# Sheet2.net
KiCad netlist of a schematic drawn in Altium Designer
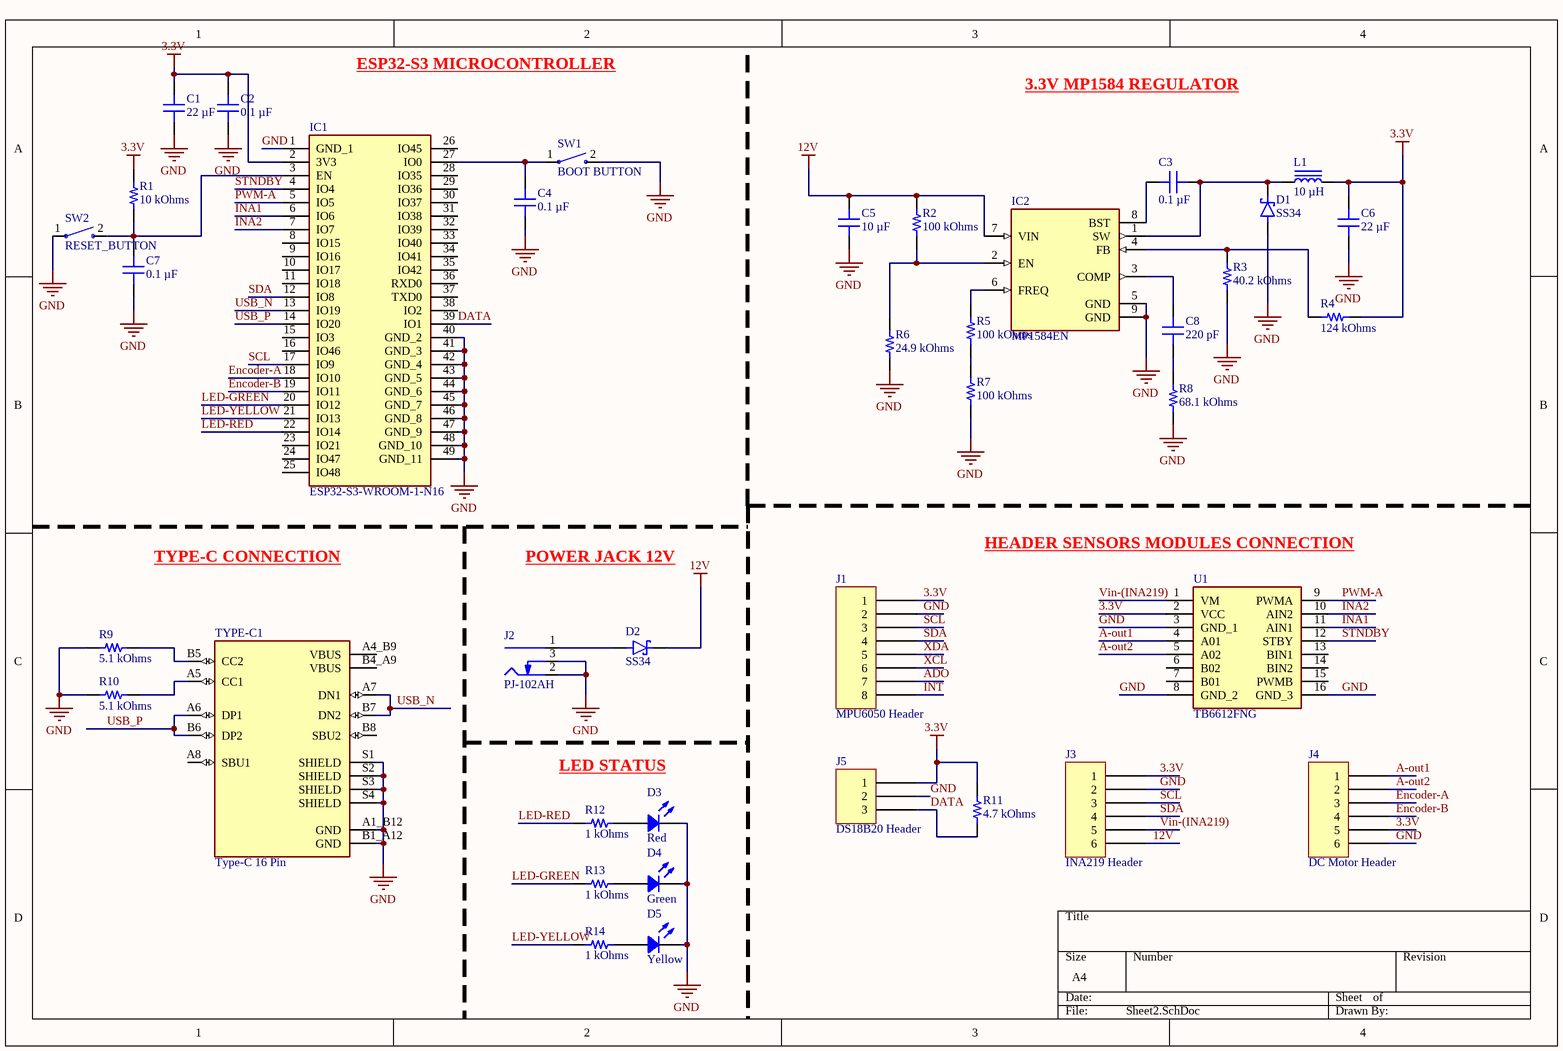
[diagram p0: Sheet2.SchDoc]

(export (version "E")
  (design (tool "Eeschema 10.0.6"))
  (components
    (comp (ref "C1")
      (value "22 µF")
      (footprint "CAP 1206_3216 - 0.8MM")
      (description "CAP CER 22UF 16V X5R 1206")
      (fields
        (field (name "PART NUMBER") "CL31A226KOCLFNC")
        (field (name "CAPACITANCE") "22 µF")
        (field (name "MANUFACTURER") "Samsung Electro-Mechanics")
      )
      (libsource (lib "Celestial Altium Library - altium_library") (part "Capacitor"))
    )
    (comp (ref "C2")
      (value "0.1 µF")
      (footprint "CAP 1206_3216 - 0.8MM")
      (description "MLCC 1206 100V 100NF X7R")
      (fields
        (field (name "PART NUMBER") "1206B104J101N")
        (field (name "CAPACITANCE") "0.1 µF")
        (field (name "MANUFACTURER") "Knowles Novacap")
      )
      (libsource (lib "Celestial Altium Library - altium_library") (part "Capacitor"))
    )
    (comp (ref "C3")
      (value "0.1 µF")
      (footprint "CAP 1206_3216 - 0.8MM")
      (description "MLCC 1206 100V 100NF X7R")
      (fields
        (field (name "PART NUMBER") "1206B104J101N")
        (field (name "CAPACITANCE") "0.1 µF")
        (field (name "MANUFACTURER") "Knowles Novacap")
      )
      (libsource (lib "Celestial Altium Library - altium_library") (part "Capacitor"))
    )
    (comp (ref "C4")
      (value "0.1 µF")
      (footprint "CAP 1206_3216 - 0.8MM")
      (description "MLCC 1206 100V 100NF X7R")
      (fields
        (field (name "PART NUMBER") "1206B104J101N")
        (field (name "CAPACITANCE") "0.1 µF")
        (field (name "MANUFACTURER") "Knowles Novacap")
      )
      (libsource (lib "Celestial Altium Library - altium_library") (part "Capacitor"))
    )
    (comp (ref "C5")
      (value "10 µF")
      (footprint "CAP 1206_3216 - 0.8MM")
      (description "CAP CER 10UF 16V X5R 1206")
      (fields
        (field (name "PART NUMBER") "EMK316BJ106MD-T")
        (field (name "CAPACITANCE") "10 µF")
        (field (name "MANUFACTURER") "Taiyo Yuden")
      )
      (libsource (lib "Celestial Altium Library - altium_library") (part "Capacitor"))
    )
    (comp (ref "C6")
      (value "22 µF")
      (footprint "CAP 1206_3216 - 0.8MM")
      (description "CAP CER 22UF 16V X5R 1206")
      (fields
        (field (name "PART NUMBER") "CL31A226MOCLNNC")
        (field (name "CAPACITANCE") "22 µF")
        (field (name "MANUFACTURER") "Samsung Electro-Mechanics")
      )
      (libsource (lib "Celestial Altium Library - altium_library") (part "Capacitor"))
    )
    (comp (ref "C7")
      (value "0.1 µF")
      (footprint "CAP 1206_3216 - 0.8MM")
      (description "MLCC 1206 100V 100NF X7R")
      (fields
        (field (name "PART NUMBER") "1206B104J101N")
        (field (name "CAPACITANCE") "0.1 µF")
        (field (name "MANUFACTURER") "Knowles Novacap")
      )
      (libsource (lib "Celestial Altium Library - altium_library") (part "Capacitor"))
    )
    (comp (ref "C8")
      (value "220 pF")
      (footprint "CAP 1206_3216 - 0.8MM")
      (description "CAP CER 220PF 500V C0G/NPO 1206")
      (fields
        (field (name "PART NUMBER") "AC1206JRNPOBBN221")
        (field (name "CAPACITANCE") "220 pF")
        (field (name "MANUFACTURER") "Yageo")
      )
      (libsource (lib "Celestial Altium Library - altium_library") (part "Capacitor"))
    )
    (comp (ref "D1") (value "SS34") (footprint "SS34") (libsource (lib "My_Library") (part "SS34")))
    (comp (ref "D2") (value "SS34") (footprint "SS34") (libsource (lib "My_Library") (part "SS34")))
    (comp (ref "D3")
      (value "Red")
      (footprint "LED 1206_3216 RED")
      (description "LED RED CLEAR 2SMD")
      (fields
        (field (name "PART NUMBER") "24-21SURC/S530-A2/TR8")
        (field (name "MANUFACTURER") "Everlight Electronics Co Ltd")
      )
      (libsource (lib "Celestial Altium Library - altium_library") (part "LED"))
    )
    (comp (ref "D4")
      (value "Green")
      (footprint "LED 1206_3216 GREEN")
      (description "LED GREEN CLEAR 2SMD")
      (fields (field (name "PART NUMBER") "XZVG55W-A2") (field (name "MANUFACTURER") "SunLED"))
      (libsource (lib "Celestial Altium Library - altium_library") (part "LED"))
    )
    (comp (ref "D5")
      (value "Yellow")
      (footprint "LED 1206_3216 YELLOW")
      (description "LED YELLOW CLEAR 2SMD")
      (fields
        (field (name "PART NUMBER") "25-21UYC/S530-A2/TR8")
        (field (name "MANUFACTURER") "Everlight Electronics Co Ltd")
      )
      (libsource (lib "Celestial Altium Library - altium_library") (part "LED"))
    )
    (comp (ref "IC1")
      (value "ESP32-S3-WROOM-1-N16")
      (footprint "SamacSys:ESP32S3WROOM1N16")
      (description "Integrated Circuit")
      (fields (field (name "MOUSER PART NUMBER") "356-ESP32S3WROOM1N16"))
      (libsource (lib "*") (part "ESP32-S3-WROOM-1-N16"))
    )
    (comp (ref "IC2")
      (value "MP1584EN")
      (footprint "MP1584EN")
      (libsource (lib "My_Library") (part "MP1584EN"))
    )
    (comp (ref "J1")
      (value "MPU6050 Header")
      (footprint "SULLINS NPPN081BFCN")
      (description "CONN HDR 8POS 0.079 GOLD PCB")
      (fields
        (field (name "PART NUMBER") "NPPN081BFCN-RC")
        (field (name "MANUFACTURER") "Sullins Connector Solutions")
      )
      (libsource (lib "Celestial Altium Library - altium_library") (part "8 Pin"))
    )
    (comp (ref "J2")
      (value "PJ-102AH")
      (footprint "CUI PJ-102AH")
      (description "CONN PWR JACK 2X5.5MM SOLDER")
      (fields (field (name "MANUFACTURER") "CUI Devices"))
      (libsource (lib "Celestial Altium Library - altium_library") (part "Barrel Connector"))
    )
    (comp (ref "J3")
      (value "INA219 Header")
      (footprint "SULLINS NPPN061BFCN")
      (description "CONN HDR 6POS 0.079 GOLD PCB")
      (fields
        (field (name "PART NUMBER") "NPPN061BFCN-RC")
        (field (name "MANUFACTURER") "Sullins Connector Solutions")
      )
      (libsource (lib "Celestial Altium Library - altium_library") (part "6 Pin"))
    )
    (comp (ref "J4")
      (value "DC Motor Header")
      (footprint "SULLINS NPPN061BFCN")
      (description "CONN HDR 6POS 0.079 GOLD PCB")
      (fields
        (field (name "PART NUMBER") "NPPN061BFCN-RC")
        (field (name "MANUFACTURER") "Sullins Connector Solutions")
      )
      (libsource (lib "Celestial Altium Library - altium_library") (part "6 Pin"))
    )
    (comp (ref "J5")
      (value "DS18B20 Header")
      (footprint "SULLINS NPPN031BFCN")
      (description "CONN HDR 3POS 0.079 GOLD PCB")
      (fields
        (field (name "PART NUMBER") "NPPN031BFCN-RC")
        (field (name "MANUFACTURER") "Sullins Connector Solutions")
      )
      (libsource (lib "Celestial Altium Library - altium_library") (part "3 Pin"))
    )
    (comp (ref "L1")
      (value "10 µH")
      (footprint "BOURNS SRP5030T")
      (description "FIXED IND 10UH 2.75A 128MOHM SMD")
      (fields (field (name "PART NUMBER") "SRP5030T-100M") (field (name "MANUFACTURER") "Bourns Inc."))
      (libsource (lib "Celestial Altium Library - altium_library") (part "Inductor"))
    )
    (comp (ref "R1")
      (value "10 kOhms")
      (footprint "RES 1206_3216")
      (description "RES SMD 10K OHM 1% 1/4W 1206")
      (fields
        (field (name "PART NUMBER") "CRG1206F10K")
        (field (name "MANUFACTURER") "TE Connectivity Passive Product")
      )
      (libsource (lib "Celestial Altium Library - altium_library") (part "Resistor"))
    )
    (comp (ref "R2")
      (value "100 kOhms")
      (footprint "RES 1206_3216")
      (description "RES 100K OHM 0.1% 1/8W 1206")
      (fields
        (field (name "PART NUMBER") "RNCS1206BKE100K")
        (field (name "MANUFACTURER") "Stackpole Electronics Inc")
      )
      (libsource (lib "Celestial Altium Library - altium_library") (part "Resistor"))
    )
    (comp (ref "R3")
      (value "40.2 kOhms")
      (footprint "RES 1206_3216")
      (description "RCS1206 100 40K2 1% ET1 E3")
      (fields (field (name "PART NUMBER") "RCS120640K2FKEA") (field (name "MANUFACTURER") "Vishay Dale"))
      (libsource (lib "Celestial Altium Library - altium_library") (part "Resistor"))
    )
    (comp (ref "R4")
      (value "124 kOhms")
      (footprint "RES 1206_3216")
      (description "RES SMD 124K OHM 1% 1/4W 1206")
      (fields (field (name "PART NUMBER") "CRCW1206124KFKEA") (field (name "MANUFACTURER") "Vishay Dale"))
      (libsource (lib "Celestial Altium Library - altium_library") (part "Resistor"))
    )
    (comp (ref "R5")
      (value "100 kOhms")
      (footprint "RES 1206_3216")
      (description "RES 100K OHM 0.1% 1/8W 1206")
      (fields
        (field (name "PART NUMBER") "RNCS1206BKE100K")
        (field (name "MANUFACTURER") "Stackpole Electronics Inc")
      )
      (libsource (lib "Celestial Altium Library - altium_library") (part "Resistor"))
    )
    (comp (ref "R6")
      (value "24.9 kOhms")
      (footprint "RES 1206_3216")
      (description "RCS1206 100 24K9 1% ET1 E3")
      (fields (field (name "PART NUMBER") "RCS120624K9FKEA") (field (name "MANUFACTURER") "Vishay Dale"))
      (libsource (lib "Celestial Altium Library - altium_library") (part "Resistor"))
    )
    (comp (ref "R7")
      (value "100 kOhms")
      (footprint "RES 1206_3216")
      (description "RES 100K OHM 0.1% 1/8W 1206")
      (fields
        (field (name "PART NUMBER") "RNCS1206BKE100K")
        (field (name "MANUFACTURER") "Stackpole Electronics Inc")
      )
      (libsource (lib "Celestial Altium Library - altium_library") (part "Resistor"))
    )
    (comp (ref "R8")
      (value "68.1 kOhms")
      (footprint "RES 1206_3216")
      (description "RES 68.1K OHM 0.1% 1/4W 1206")
      (fields
        (field (name "PART NUMBER") "RN73H2BTTD6812B25")
        (field (name "MANUFACTURER") "KOA Speer Electronics, Inc.")
      )
      (libsource (lib "Celestial Altium Library - altium_library") (part "Resistor"))
    )
    (comp (ref "R9")
      (value "5.1 kOhms")
      (footprint "YAGEO RES 1206_3216")
      (description "RES 5.1K OHM 5% 1/2W 1206")
      (fields (field (name "PART NUMBER") "SR1206JR-7W5K1L") (field (name "MANUFACTURER") "Yageo"))
      (libsource (lib "Celestial Altium Library - altium_library") (part "Resistor"))
    )
    (comp (ref "R10")
      (value "5.1 kOhms")
      (footprint "YAGEO RES 1206_3216")
      (description "RES 5.1K OHM 5% 1/2W 1206")
      (fields (field (name "PART NUMBER") "SR1206JR-7W5K1L") (field (name "MANUFACTURER") "Yageo"))
      (libsource (lib "Celestial Altium Library - altium_library") (part "Resistor"))
    )
    (comp (ref "R11")
      (value "4.7 kOhms")
      (footprint "RES 1206_3216")
      (description "RES SMD 4.7K OHM 1% 1/4W 1206")
      (fields
        (field (name "PART NUMBER") "CRG1206F4K7")
        (field (name "MANUFACTURER") "TE Connectivity Passive Product")
      )
      (libsource (lib "Celestial Altium Library - altium_library") (part "Resistor"))
    )
    (comp (ref "R12")
      (value "1 kOhms")
      (footprint "RES 1206_3216")
      (description "RES 1K OHM 0.1% 1/8W 1206")
      (fields
        (field (name "PART NUMBER") "RNCS1206BKE1K00")
        (field (name "MANUFACTURER") "Stackpole Electronics Inc")
      )
      (libsource (lib "Celestial Altium Library - altium_library") (part "Resistor"))
    )
    (comp (ref "R13")
      (value "1 kOhms")
      (footprint "RES 1206_3216")
      (description "RES 1K OHM 0.1% 1/8W 1206")
      (fields
        (field (name "PART NUMBER") "RNCS1206BKE1K00")
        (field (name "MANUFACTURER") "Stackpole Electronics Inc")
      )
      (libsource (lib "Celestial Altium Library - altium_library") (part "Resistor"))
    )
    (comp (ref "R14")
      (value "1 kOhms")
      (footprint "RES 1206_3216")
      (description "RES 1K OHM 0.1% 1/8W 1206")
      (fields
        (field (name "PART NUMBER") "RNCS1206BKE1K00")
        (field (name "MANUFACTURER") "Stackpole Electronics Inc")
      )
      (libsource (lib "Celestial Altium Library - altium_library") (part "Resistor"))
    )
    (comp (ref "SW1")
      (value "BOOT BUTTON")
      (footprint "SW_1437566-3")
      (libsource (lib "My_Library") (part "RESET_BUTTON"))
    )
    (comp (ref "SW2")
      (value "RESET_BUTTON")
      (footprint "SW_1437566-3")
      (libsource (lib "My_Library") (part "RESET_BUTTON"))
    )
    (comp (ref "TYPE-C1")
      (value "Type-C 16 Pin")
      (footprint "Type-C 16 Pin")
      (libsource (lib "My_Library") (part "Type-C 16 Pin"))
    )
    (comp (ref "U1")
      (value "TB6612FNG")
      (footprint "SamacSys:ROB14450")
      (description "Undefined or Miscellaneous")
      (fields
        (field (name "MANUFACTURER_PART_NUMBER") "ROB-14450")
        (field (name "MOUSER PART NUMBER") "474-ROB-14450")
      )
      (libsource (lib "SamacSys") (part "ROB-14450"))
    )
  )
  (nets
    (net (code "1") (name "/A-out1") (class "Default")
      (node (ref "J4") (pin "1") (pinfunction "1_1") (pintype "passive"))
      (node (ref "U1") (pin "4") (pinfunction "A01_4") (pintype "passive"))
    )
    (net (code "2") (name "/A-out2") (class "Default")
      (node (ref "J4") (pin "2") (pinfunction "2_2") (pintype "passive"))
      (node (ref "U1") (pin "5") (pinfunction "A02_5") (pintype "passive"))
    )
    (net (code "3") (name "/ADO") (class "Default")
      (node (ref "J1") (pin "7") (pinfunction "7_7") (pintype "passive"))
    )
    (net (code "4") (name "/DATA") (class "Default")
      (node (ref "IC1") (pin "39") (pinfunction "IO1_39") (pintype "passive"))
      (node (ref "J5") (pin "3") (pinfunction "3_3") (pintype "passive"))
      (node (ref "R11") (pin "1") (pinfunction "1_1") (pintype "passive"))
    )
    (net (code "5") (name "/Encoder-A") (class "Default")
      (node (ref "IC1") (pin "18") (pinfunction "IO10_18") (pintype "passive"))
      (node (ref "J4") (pin "3") (pinfunction "3_3") (pintype "passive"))
    )
    (net (code "6") (name "/Encoder-B") (class "Default")
      (node (ref "IC1") (pin "19") (pinfunction "IO11_19") (pintype "passive"))
      (node (ref "J4") (pin "4") (pinfunction "4_4") (pintype "passive"))
    )
    (net (code "7") (name "/INA1") (class "Default")
      (node (ref "IC1") (pin "6") (pinfunction "IO6_6") (pintype "passive"))
      (node (ref "U1") (pin "11") (pinfunction "AIN1_11") (pintype "passive"))
    )
    (net (code "8") (name "/INA2") (class "Default")
      (node (ref "IC1") (pin "7") (pinfunction "IO7_7") (pintype "passive"))
      (node (ref "U1") (pin "10") (pinfunction "AIN2_10") (pintype "passive"))
    )
    (net (code "9") (name "/INT") (class "Default")
      (node (ref "J1") (pin "8") (pinfunction "8_8") (pintype "passive"))
    )
    (net (code "10") (name "/LED-GREEN") (class "Default")
      (node (ref "IC1") (pin "20") (pinfunction "IO12_20") (pintype "passive"))
      (node (ref "R13") (pin "1") (pinfunction "1_1") (pintype "passive"))
    )
    (net (code "11") (name "/LED-RED") (class "Default")
      (node (ref "IC1") (pin "22") (pinfunction "IO14_22") (pintype "passive"))
      (node (ref "R12") (pin "1") (pinfunction "1_1") (pintype "passive"))
    )
    (net (code "12") (name "/LED-YELLOW") (class "Default")
      (node (ref "IC1") (pin "21") (pinfunction "IO13_21") (pintype "passive"))
      (node (ref "R14") (pin "1") (pinfunction "1_1") (pintype "passive"))
    )
    (net (code "13") (name "/PWM-A") (class "Default")
      (node (ref "IC1") (pin "5") (pinfunction "IO5_5") (pintype "passive"))
      (node (ref "U1") (pin "9") (pinfunction "PWMA_9") (pintype "passive"))
    )
    (net (code "14") (name "/SCL") (class "Default")
      (node (ref "IC1") (pin "17") (pinfunction "IO9_17") (pintype "passive"))
      (node (ref "J1") (pin "3") (pinfunction "3_3") (pintype "passive"))
      (node (ref "J3") (pin "3") (pinfunction "3_3") (pintype "passive"))
    )
    (net (code "15") (name "/SDA") (class "Default")
      (node (ref "IC1") (pin "12") (pinfunction "IO8_12") (pintype "passive"))
      (node (ref "J1") (pin "4") (pinfunction "4_4") (pintype "passive"))
      (node (ref "J3") (pin "4") (pinfunction "4_4") (pintype "passive"))
    )
    (net (code "16") (name "/STNDBY") (class "Default")
      (node (ref "IC1") (pin "4") (pinfunction "IO4_4") (pintype "passive"))
      (node (ref "U1") (pin "12") (pinfunction "STBY_12") (pintype "passive"))
    )
    (net (code "17") (name "/USB_N") (class "Default")
      (node (ref "IC1") (pin "13") (pinfunction "IO19_13") (pintype "passive"))
      (node (ref "TYPE-C1") (pin "A7") (pinfunction "DN1_A7") (pintype "bidirectional"))
      (node (ref "TYPE-C1") (pin "B7") (pinfunction "DN2_B7") (pintype "bidirectional"))
    )
    (net (code "18") (name "/USB_P") (class "Default")
      (node (ref "IC1") (pin "14") (pinfunction "IO20_14") (pintype "passive"))
      (node (ref "TYPE-C1") (pin "A6") (pinfunction "DP1_A6") (pintype "bidirectional"))
      (node (ref "TYPE-C1") (pin "B6") (pinfunction "DP2_B6") (pintype "bidirectional"))
    )
    (net (code "19") (name "/Vin-(INA219)") (class "Default")
      (node (ref "J3") (pin "5") (pinfunction "5_5") (pintype "passive"))
      (node (ref "U1") (pin "1") (pinfunction "VM_1") (pintype "passive"))
    )
    (net (code "20") (name "/XCL") (class "Default")
      (node (ref "J1") (pin "6") (pinfunction "6_6") (pintype "passive"))
    )
    (net (code "21") (name "/XDA") (class "Default")
      (node (ref "J1") (pin "5") (pinfunction "5_5") (pintype "passive"))
    )
    (net (code "22") (name "3.3V") (class "Default")
      (node (ref "C1") (pin "2") (pinfunction "2_2") (pintype "passive"))
      (node (ref "C2") (pin "2") (pinfunction "2_2") (pintype "passive"))
      (node (ref "C6") (pin "2") (pinfunction "2_2") (pintype "passive"))
      (node (ref "IC1") (pin "2") (pinfunction "3V3_2") (pintype "passive"))
      (node (ref "J1") (pin "1") (pinfunction "1_1") (pintype "passive"))
      (node (ref "J3") (pin "1") (pinfunction "1_1") (pintype "passive"))
      (node (ref "J4") (pin "5") (pinfunction "5_5") (pintype "passive"))
      (node (ref "J5") (pin "1") (pinfunction "1_1") (pintype "passive"))
      (node (ref "L1") (pin "2") (pinfunction "2_2") (pintype "passive"))
      (node (ref "R1") (pin "2") (pinfunction "2_2") (pintype "passive"))
      (node (ref "R11") (pin "2") (pinfunction "2_2") (pintype "passive"))
      (node (ref "R4") (pin "2") (pinfunction "2_2") (pintype "passive"))
      (node (ref "U1") (pin "2") (pinfunction "VCC_2") (pintype "passive"))
    )
    (net (code "23") (name "12V") (class "Default")
      (node (ref "C5") (pin "2") (pinfunction "2_2") (pintype "passive"))
      (node (ref "D2") (pin "C") (pinfunction "K_C") (pintype "passive"))
      (node (ref "IC2") (pin "7") (pinfunction "VIN_7") (pintype "input"))
      (node (ref "J3") (pin "6") (pinfunction "6_6") (pintype "passive"))
      (node (ref "R2") (pin "2") (pinfunction "2_2") (pintype "passive"))
    )
    (net (code "24") (name "GND") (class "Default")
      (node (ref "C1") (pin "1") (pinfunction "1_1") (pintype "passive"))
      (node (ref "C2") (pin "1") (pinfunction "1_1") (pintype "passive"))
      (node (ref "C4") (pin "2") (pinfunction "2_2") (pintype "passive"))
      (node (ref "C5") (pin "1") (pinfunction "1_1") (pintype "passive"))
      (node (ref "C6") (pin "1") (pinfunction "1_1") (pintype "passive"))
      (node (ref "C7") (pin "2") (pinfunction "2_2") (pintype "passive"))
      (node (ref "D1") (pin "A") (pinfunction "A_A") (pintype "passive"))
      (node (ref "D3") (pin "2") (pinfunction "2_2") (pintype "passive"))
      (node (ref "D4") (pin "2") (pinfunction "2_2") (pintype "passive"))
      (node (ref "D5") (pin "2") (pinfunction "2_2") (pintype "passive"))
      (node (ref "IC1") (pin "1") (pinfunction "GND_1_1") (pintype "passive"))
      (node (ref "IC1") (pin "40") (pinfunction "GND_2_40") (pintype "passive"))
      (node (ref "IC1") (pin "41") (pinfunction "GND_3_41") (pintype "passive"))
      (node (ref "IC1") (pin "42") (pinfunction "GND_4_42") (pintype "passive"))
      (node (ref "IC1") (pin "43") (pinfunction "GND_5_43") (pintype "passive"))
      (node (ref "IC1") (pin "44") (pinfunction "GND_6_44") (pintype "passive"))
      (node (ref "IC1") (pin "45") (pinfunction "GND_7_45") (pintype "passive"))
      (node (ref "IC1") (pin "46") (pinfunction "GND_8_46") (pintype "passive"))
      (node (ref "IC1") (pin "47") (pinfunction "GND_9_47") (pintype "passive"))
      (node (ref "IC1") (pin "48") (pinfunction "GND_10_48") (pintype "passive"))
      (node (ref "IC1") (pin "49") (pinfunction "GND_11_49") (pintype "passive"))
      (node (ref "IC2") (pin "5") (pinfunction "GND_5") (pintype "power_in"))
      (node (ref "IC2") (pin "9") (pinfunction "GND_9") (pintype "power_in"))
      (node (ref "J1") (pin "2") (pinfunction "2_2") (pintype "passive"))
      (node (ref "J2") (pin "2") (pinfunction "Outer_2") (pintype "passive"))
      (node (ref "J2") (pin "3") (pinfunction "SW_3") (pintype "passive"))
      (node (ref "J3") (pin "2") (pinfunction "2_2") (pintype "passive"))
      (node (ref "J4") (pin "6") (pinfunction "6_6") (pintype "passive"))
      (node (ref "J5") (pin "2") (pinfunction "2_2") (pintype "passive"))
      (node (ref "R10") (pin "1") (pinfunction "1_1") (pintype "passive"))
      (node (ref "R3") (pin "2") (pinfunction "2_2") (pintype "passive"))
      (node (ref "R6") (pin "1") (pinfunction "1_1") (pintype "passive"))
      (node (ref "R7") (pin "1") (pinfunction "1_1") (pintype "passive"))
      (node (ref "R8") (pin "1") (pinfunction "1_1") (pintype "passive"))
      (node (ref "R9") (pin "1") (pinfunction "1_1") (pintype "passive"))
      (node (ref "SW1") (pin "2") (pinfunction "2_2") (pintype "passive"))
      (node (ref "SW2") (pin "1") (pinfunction "1_1") (pintype "passive"))
      (node (ref "TYPE-C1") (pin "A1_B12") (pinfunction "GND_A1_B12") (pintype "power_in"))
      (node (ref "TYPE-C1") (pin "B1_A12") (pinfunction "GND_B1_A12") (pintype "power_in"))
      (node (ref "TYPE-C1") (pin "S1") (pinfunction "SHIELD_S1") (pintype "passive"))
      (node (ref "TYPE-C1") (pin "S2") (pinfunction "SHIELD_S2") (pintype "passive"))
      (node (ref "TYPE-C1") (pin "S3") (pinfunction "SHIELD_S3") (pintype "passive"))
      (node (ref "TYPE-C1") (pin "S4") (pinfunction "SHIELD_S4") (pintype "passive"))
      (node (ref "U1") (pin "16") (pinfunction "GND_3_16") (pintype "passive"))
      (node (ref "U1") (pin "3") (pinfunction "GND_1_3") (pintype "passive"))
      (node (ref "U1") (pin "8") (pinfunction "GND_2_8") (pintype "passive"))
    )
    (net (code "25") (name "Net-(C8-Pad1)") (class "Default")
      (node (ref "C8") (pin "1") (pinfunction "1_1") (pintype "passive"))
      (node (ref "R8") (pin "2") (pinfunction "2_2") (pintype "passive"))
    )
    (net (code "26") (name "Net-(D1-K)") (class "Default")
      (node (ref "C3") (pin "2") (pinfunction "2_2") (pintype "passive"))
      (node (ref "D1") (pin "C") (pinfunction "K_C") (pintype "passive"))
      (node (ref "IC2") (pin "1") (pinfunction "SW_1") (pintype "output"))
      (node (ref "L1") (pin "1") (pinfunction "1_1") (pintype "passive"))
    )
    (net (code "27") (name "Net-(D3-Pad1)") (class "Default")
      (node (ref "D3") (pin "1") (pinfunction "1_1") (pintype "passive"))
      (node (ref "R12") (pin "2") (pinfunction "2_2") (pintype "passive"))
    )
    (net (code "28") (name "Net-(D4-Pad1)") (class "Default")
      (node (ref "D4") (pin "1") (pinfunction "1_1") (pintype "passive"))
      (node (ref "R13") (pin "2") (pinfunction "2_2") (pintype "passive"))
    )
    (net (code "29") (name "Net-(D5-Pad1)") (class "Default")
      (node (ref "D5") (pin "1") (pinfunction "1_1") (pintype "passive"))
      (node (ref "R14") (pin "2") (pinfunction "2_2") (pintype "passive"))
    )
    (net (code "30") (name "Net-(IC1-EN)") (class "Default")
      (node (ref "C7") (pin "1") (pinfunction "1_1") (pintype "passive"))
      (node (ref "IC1") (pin "3") (pinfunction "EN_3") (pintype "passive"))
      (node (ref "R1") (pin "1") (pinfunction "1_1") (pintype "passive"))
      (node (ref "SW2") (pin "2") (pinfunction "2_2") (pintype "passive"))
    )
    (net (code "31") (name "Net-(IC1-IO0)") (class "Default")
      (node (ref "C4") (pin "1") (pinfunction "1_1") (pintype "passive"))
      (node (ref "IC1") (pin "27") (pinfunction "IO0_27") (pintype "passive"))
      (node (ref "SW1") (pin "1") (pinfunction "1_1") (pintype "passive"))
    )
    (net (code "32") (name "Net-(IC2-BST)") (class "Default")
      (node (ref "C3") (pin "1") (pinfunction "1_1") (pintype "passive"))
      (node (ref "IC2") (pin "8") (pinfunction "BST_8") (pintype "passive"))
    )
    (net (code "33") (name "Net-(IC2-COMP)") (class "Default")
      (node (ref "C8") (pin "2") (pinfunction "2_2") (pintype "passive"))
      (node (ref "IC2") (pin "3") (pinfunction "COMP_3") (pintype "output"))
    )
    (net (code "34") (name "Net-(IC2-EN)") (class "Default")
      (node (ref "IC2") (pin "2") (pinfunction "EN_2") (pintype "input"))
      (node (ref "R2") (pin "1") (pinfunction "1_1") (pintype "passive"))
      (node (ref "R6") (pin "2") (pinfunction "2_2") (pintype "passive"))
    )
    (net (code "35") (name "Net-(IC2-FB)") (class "Default")
      (node (ref "IC2") (pin "4") (pinfunction "FB_4") (pintype "input"))
      (node (ref "R3") (pin "1") (pinfunction "1_1") (pintype "passive"))
      (node (ref "R4") (pin "1") (pinfunction "1_1") (pintype "passive"))
    )
    (net (code "36") (name "Net-(IC2-FREQ)") (class "Default")
      (node (ref "IC2") (pin "6") (pinfunction "FREQ_6") (pintype "input"))
      (node (ref "R5") (pin "2") (pinfunction "2_2") (pintype "passive"))
    )
    (net (code "37") (name "Net-(J2-Centre)") (class "Default")
      (node (ref "D2") (pin "A") (pinfunction "A_A") (pintype "passive"))
      (node (ref "J2") (pin "1") (pinfunction "Centre_1") (pintype "passive"))
    )
    (net (code "38") (name "Net-(R5-Pad1)") (class "Default")
      (node (ref "R5") (pin "1") (pinfunction "1_1") (pintype "passive"))
      (node (ref "R7") (pin "2") (pinfunction "2_2") (pintype "passive"))
    )
    (net (code "39") (name "Net-(TYPE-C1-CC1)") (class "Default")
      (node (ref "R10") (pin "2") (pinfunction "2_2") (pintype "passive"))
      (node (ref "TYPE-C1") (pin "A5") (pinfunction "CC1_A5") (pintype "bidirectional"))
    )
    (net (code "40") (name "Net-(TYPE-C1-CC2)") (class "Default")
      (node (ref "R9") (pin "2") (pinfunction "2_2") (pintype "passive"))
      (node (ref "TYPE-C1") (pin "B5") (pinfunction "CC2_B5") (pintype "bidirectional"))
    )
    (net (code "41") (name "unconnected-(IC1-IO2-Pad38)") (class "Default")
      (node (ref "IC1") (pin "38") (pinfunction "IO2_38") (pintype "passive"))
    )
    (net (code "42") (name "unconnected-(IC1-IO3-Pad15)") (class "Default")
      (node (ref "IC1") (pin "15") (pinfunction "IO3_15") (pintype "passive"))
    )
    (net (code "43") (name "unconnected-(IC1-IO15-Pad8)") (class "Default")
      (node (ref "IC1") (pin "8") (pinfunction "IO15_8") (pintype "passive"))
    )
    (net (code "44") (name "unconnected-(IC1-IO16-Pad9)") (class "Default")
      (node (ref "IC1") (pin "9") (pinfunction "IO16_9") (pintype "passive"))
    )
    (net (code "45") (name "unconnected-(IC1-IO17-Pad10)") (class "Default")
      (node (ref "IC1") (pin "10") (pinfunction "IO17_10") (pintype "passive"))
    )
    (net (code "46") (name "unconnected-(IC1-IO18-Pad11)") (class "Default")
      (node (ref "IC1") (pin "11") (pinfunction "IO18_11") (pintype "passive"))
    )
    (net (code "47") (name "unconnected-(IC1-IO21-Pad23)") (class "Default")
      (node (ref "IC1") (pin "23") (pinfunction "IO21_23") (pintype "passive"))
    )
    (net (code "48") (name "unconnected-(IC1-IO35-Pad28)") (class "Default")
      (node (ref "IC1") (pin "28") (pinfunction "IO35_28") (pintype "passive"))
    )
    (net (code "49") (name "unconnected-(IC1-IO36-Pad29)") (class "Default")
      (node (ref "IC1") (pin "29") (pinfunction "IO36_29") (pintype "passive"))
    )
    (net (code "50") (name "unconnected-(IC1-IO37-Pad30)") (class "Default")
      (node (ref "IC1") (pin "30") (pinfunction "IO37_30") (pintype "passive"))
    )
    (net (code "51") (name "unconnected-(IC1-IO38-Pad31)") (class "Default")
      (node (ref "IC1") (pin "31") (pinfunction "IO38_31") (pintype "passive"))
    )
    (net (code "52") (name "unconnected-(IC1-IO39-Pad32)") (class "Default")
      (node (ref "IC1") (pin "32") (pinfunction "IO39_32") (pintype "passive"))
    )
    (net (code "53") (name "unconnected-(IC1-IO40-Pad33)") (class "Default")
      (node (ref "IC1") (pin "33") (pinfunction "IO40_33") (pintype "passive"))
    )
    (net (code "54") (name "unconnected-(IC1-IO41-Pad34)") (class "Default")
      (node (ref "IC1") (pin "34") (pinfunction "IO41_34") (pintype "passive"))
    )
    (net (code "55") (name "unconnected-(IC1-IO42-Pad35)") (class "Default")
      (node (ref "IC1") (pin "35") (pinfunction "IO42_35") (pintype "passive"))
    )
    (net (code "56") (name "unconnected-(IC1-IO45-Pad26)") (class "Default")
      (node (ref "IC1") (pin "26") (pinfunction "IO45_26") (pintype "passive"))
    )
    (net (code "57") (name "unconnected-(IC1-IO46-Pad16)") (class "Default")
      (node (ref "IC1") (pin "16") (pinfunction "IO46_16") (pintype "passive"))
    )
    (net (code "58") (name "unconnected-(IC1-IO47-Pad24)") (class "Default")
      (node (ref "IC1") (pin "24") (pinfunction "IO47_24") (pintype "passive"))
    )
    (net (code "59") (name "unconnected-(IC1-IO48-Pad25)") (class "Default")
      (node (ref "IC1") (pin "25") (pinfunction "IO48_25") (pintype "passive"))
    )
    (net (code "60") (name "unconnected-(IC1-RXD0-Pad36)") (class "Default")
      (node (ref "IC1") (pin "36") (pinfunction "RXD0_36") (pintype "passive"))
    )
    (net (code "61") (name "unconnected-(IC1-TXD0-Pad37)") (class "Default")
      (node (ref "IC1") (pin "37") (pinfunction "TXD0_37") (pintype "passive"))
    )
    (net (code "62") (name "unconnected-(TYPE-C1-SBU1-PadA8)") (class "Default")
      (node (ref "TYPE-C1") (pin "A8") (pinfunction "SBU1_A8") (pintype "bidirectional"))
    )
    (net (code "63") (name "unconnected-(TYPE-C1-SBU2-PadB8)") (class "Default")
      (node (ref "TYPE-C1") (pin "B8") (pinfunction "SBU2_B8") (pintype "bidirectional"))
    )
    (net (code "64") (name "unconnected-(TYPE-C1-VBUS-PadA4_B9)") (class "Default")
      (node (ref "TYPE-C1") (pin "A4_B9") (pinfunction "VBUS_A4_B9") (pintype "power_in"))
    )
    (net (code "65") (name "unconnected-(TYPE-C1-VBUS-PadB4_A9)") (class "Default")
      (node (ref "TYPE-C1") (pin "B4_A9") (pinfunction "VBUS_B4_A9") (pintype "power_in"))
    )
    (net (code "66") (name "unconnected-(U1-B01-Pad7)") (class "Default")
      (node (ref "U1") (pin "7") (pinfunction "B01_7") (pintype "passive"))
    )
    (net (code "67") (name "unconnected-(U1-B02-Pad6)") (class "Default")
      (node (ref "U1") (pin "6") (pinfunction "B02_6") (pintype "passive"))
    )
    (net (code "68") (name "unconnected-(U1-BIN1-Pad13)") (class "Default")
      (node (ref "U1") (pin "13") (pinfunction "BIN1_13") (pintype "passive"))
    )
    (net (code "69") (name "unconnected-(U1-BIN2-Pad14)") (class "Default")
      (node (ref "U1") (pin "14") (pinfunction "BIN2_14") (pintype "passive"))
    )
    (net (code "70") (name "unconnected-(U1-PWMB-Pad15)") (class "Default")
      (node (ref "U1") (pin "15") (pinfunction "PWMB_15") (pintype "passive"))
    )
  )
)
